# side_panel_V6.net
KiCad netlist of a schematic drawn in EAGLE
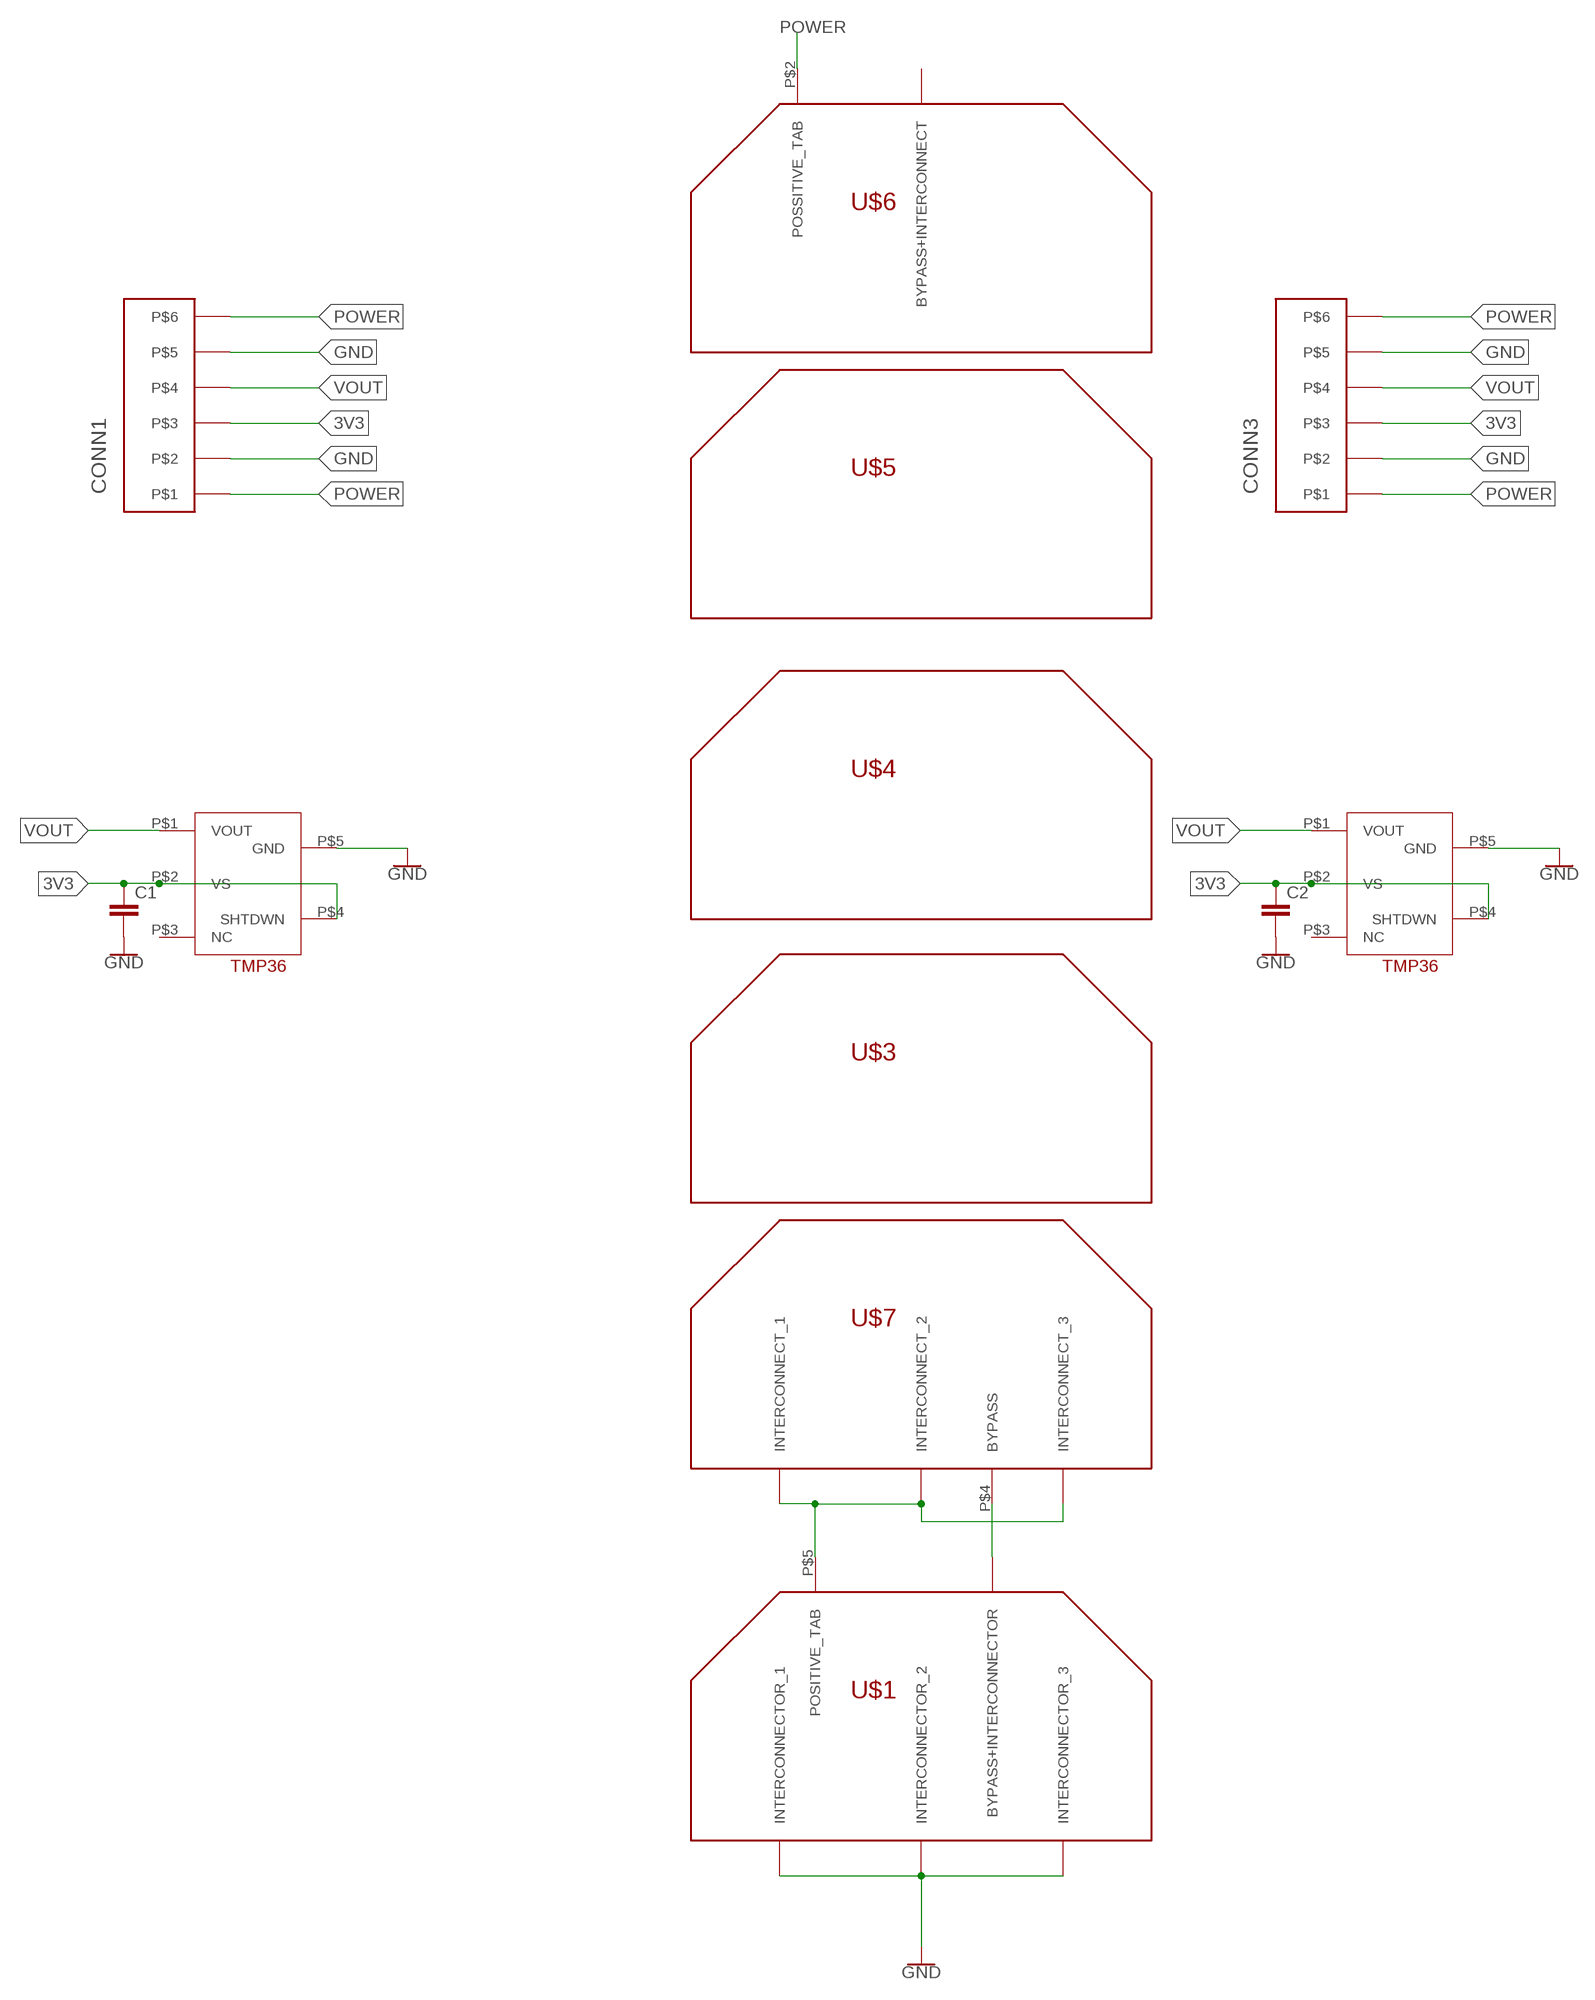
[diagram p0: schematic, sheet 1]

(export (version "E")
  (design (tool "Eeschema 10.0.6"))
  (components
    (comp (ref "C1")
      (value "CAPACITOR0805")
      (footprint "eagle-import:0805")
      (libsource (lib "eagle-import") (part "CAPACITOR0805"))
    )
    (comp (ref "C2")
      (value "CAPACITOR0805")
      (footprint "eagle-import:0805")
      (libsource (lib "eagle-import") (part "CAPACITOR0805"))
    )
    (comp (ref "CONN1")
      (value "PICOLOCK_6")
      (footprint "eagle-import:PICOLOCK_6")
      (libsource (lib "eagle-import") (part "PICOLOCK_6"))
    )
    (comp (ref "CONN3")
      (value "PICOLOCK_6")
      (footprint "eagle-import:PICOLOCK_6")
      (libsource (lib "eagle-import") (part "PICOLOCK_6"))
    )
    (comp (ref "U$1")
      (value "SOLAR_CELL_STAND-ALONE")
      (footprint "eagle-import:SOLAR_CELL_STAND-ALONE")
      (libsource (lib "eagle-import") (part "SOLAR_CELL_STAND-ALONE"))
    )
    (comp (ref "U$2")
      (value "TMP36")
      (footprint "eagle-import:SOT-23-5")
      (libsource (lib "eagle-import") (part "TMP36"))
    )
    (comp (ref "U$3")
      (value "SOALAR_CELL_OUTLINE")
      (footprint "eagle-import:SOLAR_CELL_OUTLINE")
      (libsource (lib "eagle-import") (part "SOALAR_CELL_OUTLINE"))
    )
    (comp (ref "U$4")
      (value "SOALAR_CELL_OUTLINE")
      (footprint "eagle-import:SOLAR_CELL_OUTLINE")
      (libsource (lib "eagle-import") (part "SOALAR_CELL_OUTLINE"))
    )
    (comp (ref "U$5")
      (value "SOALAR_CELL_OUTLINE")
      (footprint "eagle-import:SOLAR_CELL_OUTLINE")
      (libsource (lib "eagle-import") (part "SOALAR_CELL_OUTLINE"))
    )
    (comp (ref "U$6")
      (value "SOLAR_CELL_TOP")
      (footprint "eagle-import:SOLAR_CELL_TOP_SHORT-PAD")
      (libsource (lib "eagle-import") (part "SOLAR_CELL_TOP"))
    )
    (comp (ref "U$7")
      (value "SOLAR_CELL_BOTTOM+BYPASS")
      (footprint "eagle-import:SOLAR_CELL_BOTTOM+BYPASS")
      (libsource (lib "eagle-import") (part "SOLAR_CELL_BOTTOM+BYPASS"))
    )
    (comp (ref "U$8")
      (value "TMP36")
      (footprint "eagle-import:SOT-23-5")
      (libsource (lib "eagle-import") (part "TMP36"))
    )
  )
  (nets
    (net (code "1") (name "3V3") (class "Default")
      (node (ref "C1") (pin "1") (pinfunction "1_1") (pintype "passive"))
      (node (ref "C2") (pin "1") (pinfunction "1_1") (pintype "passive"))
      (node (ref "CONN1") (pin "P$3") (pinfunction "P$3_P$3") (pintype "bidirectional"))
      (node (ref "CONN3") (pin "P$3") (pinfunction "P$3_P$3") (pintype "bidirectional"))
      (node (ref "U$2") (pin "P$2") (pinfunction "VS_P$2") (pintype "bidirectional"))
      (node (ref "U$2") (pin "P$4") (pinfunction "SHTDWN_P$4") (pintype "bidirectional"))
      (node (ref "U$8") (pin "P$2") (pinfunction "VS_P$2") (pintype "bidirectional"))
      (node (ref "U$8") (pin "P$4") (pinfunction "SHTDWN_P$4") (pintype "bidirectional"))
    )
    (net (code "2") (name "GND") (class "Default")
      (node (ref "C1") (pin "2") (pinfunction "2_2") (pintype "passive"))
      (node (ref "C2") (pin "2") (pinfunction "2_2") (pintype "passive"))
      (node (ref "CONN1") (pin "P$2") (pinfunction "P$2_P$2") (pintype "bidirectional"))
      (node (ref "CONN1") (pin "P$5") (pinfunction "P$5_P$5") (pintype "bidirectional"))
      (node (ref "CONN3") (pin "P$2") (pinfunction "P$2_P$2") (pintype "bidirectional"))
      (node (ref "CONN3") (pin "P$5") (pinfunction "P$5_P$5") (pintype "bidirectional"))
      (node (ref "U$1") (pin "P$1") (pinfunction "INTERCONNECTOR_1_P$1") (pintype "bidirectional"))
      (node (ref "U$1") (pin "P$2") (pinfunction "INTERCONNECTOR_2_P$2") (pintype "bidirectional"))
      (node (ref "U$1") (pin "P$3") (pinfunction "INTERCONNECTOR_3_P$3") (pintype "bidirectional"))
      (node (ref "U$2") (pin "P$5") (pinfunction "GND_P$5") (pintype "bidirectional"))
      (node (ref "U$8") (pin "P$5") (pinfunction "GND_P$5") (pintype "bidirectional"))
    )
    (net (code "3") (name "Net-(U$1-BYPASS+INTERCONNECTOR)") (class "Default")
      (node (ref "U$1") (pin "P$4") (pinfunction "BYPASS+INTERCONNECTOR_P$4") (pintype "bidirectional"))
      (node (ref "U$7") (pin "P$4") (pinfunction "BYPASS_P$4") (pintype "bidirectional"))
    )
    (net (code "4") (name "Net-(U$1-POSITIVE_TAB)") (class "Default")
      (node (ref "U$1") (pin "P$5") (pinfunction "POSITIVE_TAB_P$5") (pintype "bidirectional"))
      (node (ref "U$7") (pin "P$1") (pinfunction "INTERCONNECT_1_P$1") (pintype "bidirectional"))
      (node (ref "U$7") (pin "P$2") (pinfunction "INTERCONNECT_2_P$2") (pintype "bidirectional"))
      (node (ref "U$7") (pin "P$3") (pinfunction "INTERCONNECT_3_P$3") (pintype "bidirectional"))
    )
    (net (code "5") (name "POWER") (class "Default")
      (node (ref "CONN1") (pin "P$1") (pinfunction "P$1_P$1") (pintype "bidirectional"))
      (node (ref "CONN1") (pin "P$6") (pinfunction "P$6_P$6") (pintype "bidirectional"))
      (node (ref "CONN3") (pin "P$1") (pinfunction "P$1_P$1") (pintype "bidirectional"))
      (node (ref "CONN3") (pin "P$6") (pinfunction "P$6_P$6") (pintype "bidirectional"))
      (node (ref "U$6") (pin "P$2") (pinfunction "POSSITIVE_TAB_P$2") (pintype "bidirectional"))
    )
    (net (code "6") (name "VOUT") (class "Default")
      (node (ref "CONN1") (pin "P$4") (pinfunction "P$4_P$4") (pintype "bidirectional"))
      (node (ref "CONN3") (pin "P$4") (pinfunction "P$4_P$4") (pintype "bidirectional"))
      (node (ref "U$2") (pin "P$1") (pinfunction "VOUT_P$1") (pintype "bidirectional"))
      (node (ref "U$8") (pin "P$1") (pinfunction "VOUT_P$1") (pintype "bidirectional"))
    )
    (net (code "7") (name "unconnected-(U$2-NC-PadP$3)") (class "Default")
      (node (ref "U$2") (pin "P$3") (pinfunction "NC_P$3") (pintype "bidirectional"))
    )
    (net (code "8") (name "unconnected-(U$6-BYPASS+INTERCONNECT-PadP$1)") (class "Default")
      (node (ref "U$6") (pin "P$1") (pinfunction "BYPASS+INTERCONNECT_P$1") (pintype "bidirectional"))
    )
    (net (code "9") (name "unconnected-(U$8-NC-PadP$3)") (class "Default")
      (node (ref "U$8") (pin "P$3") (pinfunction "NC_P$3") (pintype "bidirectional"))
    )
  )
)
